# 19V_Supply.net
KiCad netlist of a schematic drawn in Altium Designer
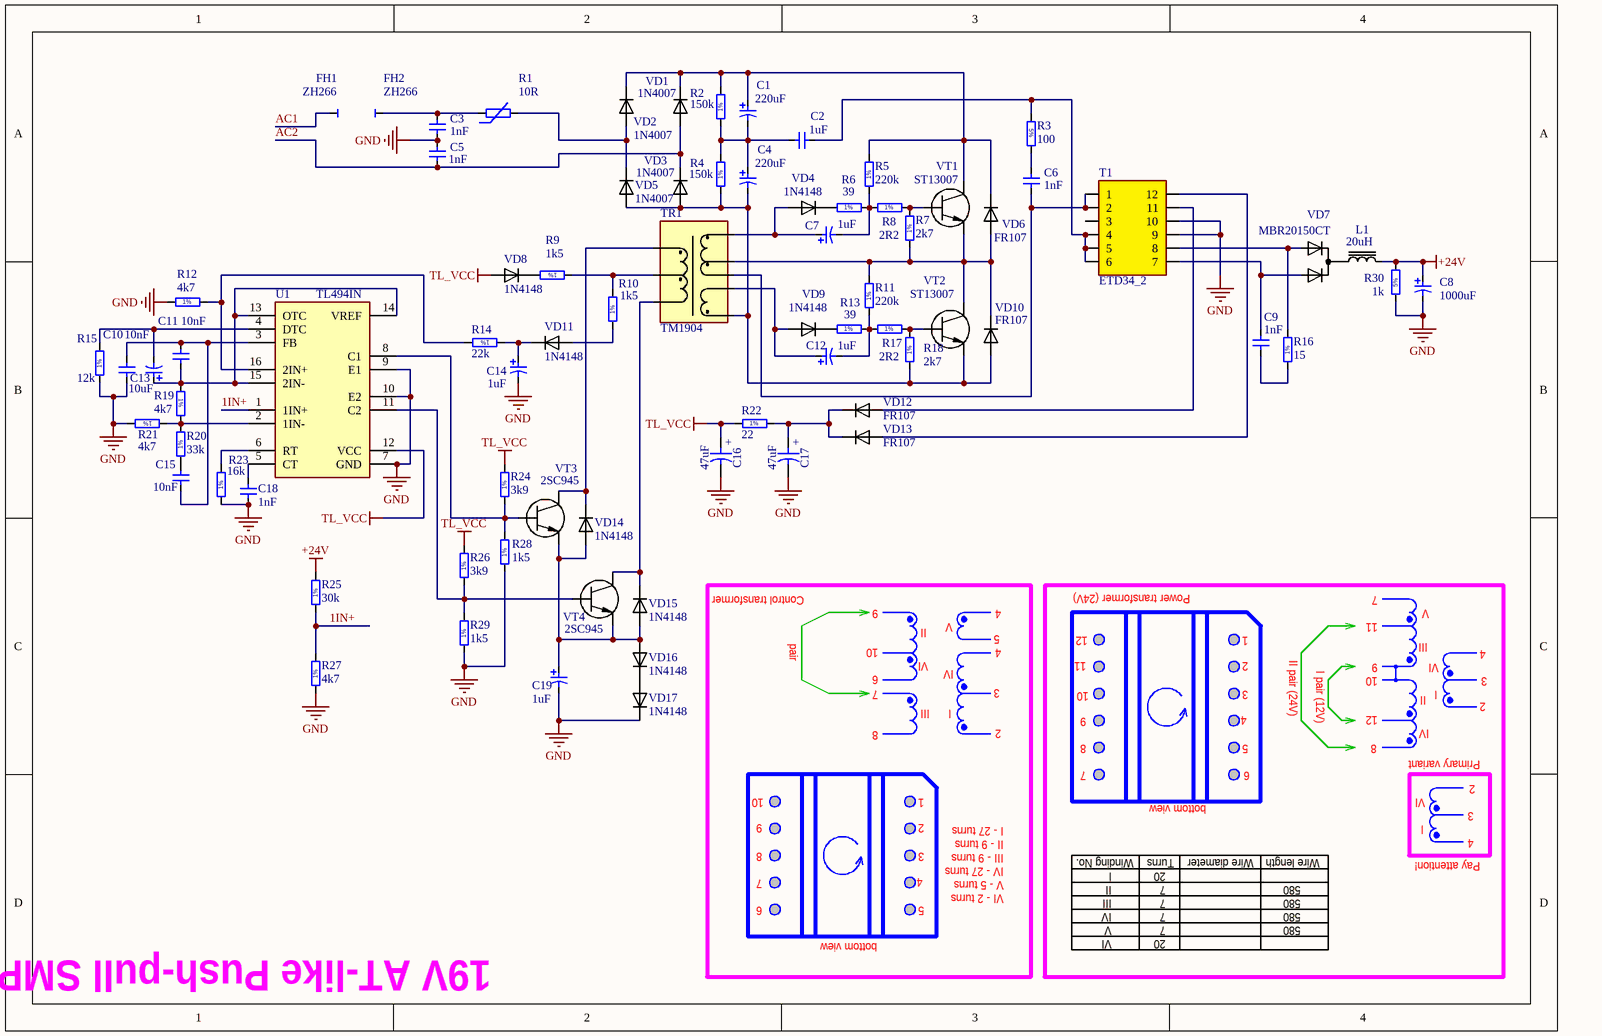
[diagram p0: 19V_Supply.SchDoc]

(export (version "E")
  (design (tool "Eeschema 10.0.6"))
  (components
    (comp (ref "C1")
      (value "220uF")
      (footprint "CAP_EL_22_25_VERT")
      (fields
        (field (name "PART NUMBER") "LG200M0220BPF-2225 (VERT MOUNTED)")
        (field (name "VOLTAGE") "200V")
      )
      (libsource (lib "Capacitor") (part "CAP_POLAR"))
    )
    (comp (ref "C2")
      (value "1uF")
      (footprint "CAPRR2000W80L2400T750H1500_CL21")
      (description "SMD 0805 Capacitor")
      (fields (field (name "PART NUMBER") "К73-17-250-1 10%") (field (name "VOLTAGE") "250V"))
      (libsource (lib "Capacitor") (part "CAP_NON_POLAR"))
    )
    (comp (ref "C3")
      (value "1nF")
      (footprint "CAP_5.0MM")
      (description "SMD 0805 Capacitor")
      (fields (field (name "PART NUMBER") "CK45-B3DD102KYNN") (field (name "VOLTAGE") "2000V"))
      (libsource (lib "Capacitor") (part "CAP_NON_POLAR"))
    )
    (comp (ref "C4")
      (value "220uF")
      (footprint "CAP_EL_22_25_VERT")
      (fields
        (field (name "PART NUMBER") "LG200M0220BPF-2225 (VERT MOUNTED)")
        (field (name "VOLTAGE") "200V")
      )
      (libsource (lib "Capacitor") (part "CAP_POLAR"))
    )
    (comp (ref "C5")
      (value "1nF")
      (footprint "CAP_5.0MM")
      (description "SMD 0805 Capacitor")
      (fields (field (name "PART NUMBER") "CK45-B3DD102KYNN") (field (name "VOLTAGE") "2000V"))
      (libsource (lib "Capacitor") (part "CAP_NON_POLAR"))
    )
    (comp (ref "C6")
      (value "1nF")
      (footprint "CAP_5.0MM")
      (description "SMD 0805 Capacitor")
      (fields (field (name "PART NUMBER") "CK45-B3DD102KYNN") (field (name "VOLTAGE") "2000V"))
      (libsource (lib "Capacitor") (part "CAP_NON_POLAR"))
    )
    (comp (ref "C7")
      (value "1uF")
      (footprint "CAP_EL_05_11_VERT")
      (fields (field (name "PART NUMBER") "SH050M1R00B2F-0511 (VERT MOUNTED)") (field (name "VOLTAGE") "50V"))
      (libsource (lib "Capacitor") (part "CAP_POLAR"))
    )
    (comp (ref "C8")
      (value "1000uF")
      (footprint "CAP_EL_13_20_VERT")
      (fields (field (name "PART NUMBER") "SK035M1000B5S-1320 (VERT MOUNTED)") (field (name "VOLTAGE") "35V"))
      (libsource (lib "Capacitor") (part "CAP_POLAR"))
    )
    (comp (ref "C9")
      (value "1nF")
      (footprint "CAP_5.0MM")
      (description "SMD 0805 Capacitor")
      (fields (field (name "PART NUMBER") "CK45-B3DD102KYNN") (field (name "VOLTAGE") "2000V"))
      (libsource (lib "Capacitor") (part "CAP_NON_POLAR"))
    )
    (comp (ref "C10")
      (value "10nF")
      (footprint "CAP_5.0MM")
      (description "SMD 0805 Capacitor")
      (fields (field (name "PART NUMBER") "TS170R1H103K8BBB0R") (field (name "VOLTAGE") "50V"))
      (libsource (lib "Capacitor") (part "CAP_NON_POLAR"))
    )
    (comp (ref "C11")
      (value "10nF")
      (footprint "CAP_5.0MM")
      (description "SMD 0805 Capacitor")
      (fields (field (name "PART NUMBER") "TS170R1H103K8BBB0R") (field (name "VOLTAGE") "50V"))
      (libsource (lib "Capacitor") (part "CAP_NON_POLAR"))
    )
    (comp (ref "C12")
      (value "1uF")
      (footprint "CAP_EL_05_11_VERT")
      (fields (field (name "PART NUMBER") "SH050M1R00B2F-0511 (VERT MOUNTED)") (field (name "VOLTAGE") "50V"))
      (libsource (lib "Capacitor") (part "CAP_POLAR"))
    )
    (comp (ref "C13")
      (value "10uF")
      (footprint "CAP_EL_05_11_VERT")
      (fields (field (name "PART NUMBER") "SH050M0010B2F-0511 (VERT MOUNTED)") (field (name "VOLTAGE") "50V"))
      (libsource (lib "Capacitor") (part "CAP_POLAR"))
    )
    (comp (ref "C14")
      (value "1uF")
      (footprint "CAP_EL_05_11_VERT")
      (fields (field (name "PART NUMBER") "SH050M1R00B2F-0511 (VERT MOUNTED)") (field (name "VOLTAGE") "50V"))
      (libsource (lib "Capacitor") (part "CAP_POLAR"))
    )
    (comp (ref "C15")
      (value "10nF")
      (footprint "CAP_5.0MM")
      (description "SMD 0805 Capacitor")
      (fields (field (name "PART NUMBER") "TS170R1H103K8BBB0R") (field (name "VOLTAGE") "50V"))
      (libsource (lib "Capacitor") (part "CAP_NON_POLAR"))
    )
    (comp (ref "C16")
      (value "47uF")
      (footprint "CAPPR250-500X1100")
      (description "Polarised capacitor")
      (fields
        (field (name "PART NUMBER") "CAER_47UF_25V_20%_250-500X1100")
        (field (name "VOLTAGE") "25V")
        (field (name "AUTHOR") "CERN DEM JLC")
      )
      (libsource (lib "Capacitors") (part "Capacitor - polarized"))
    )
    (comp (ref "C17")
      (value "47uF")
      (footprint "CAPPR250-500X1100")
      (description "Polarised capacitor")
      (fields
        (field (name "PART NUMBER") "CAER_47UF_25V_20%_250-500X1100")
        (field (name "VOLTAGE") "25V")
        (field (name "AUTHOR") "CERN DEM JLC")
      )
      (libsource (lib "Capacitors") (part "Capacitor - polarized"))
    )
    (comp (ref "C18")
      (value "1nF")
      (footprint "CAP_5.0MM")
      (description "SMD 0805 Capacitor")
      (fields (field (name "PART NUMBER") "TS170R1H102JSBNB0R") (field (name "VOLTAGE") "50V"))
      (libsource (lib "Capacitor") (part "CAP_NON_POLAR"))
    )
    (comp (ref "C19")
      (value "1uF")
      (footprint "CAP_EL_05_11_VERT")
      (fields (field (name "PART NUMBER") "SH050M1R00B2F-0511 (VERT MOUNTED)") (field (name "VOLTAGE") "50V"))
      (libsource (lib "Capacitor") (part "CAP_POLAR"))
    )
    (comp (ref "FH1") (value "ZH266") (footprint "ZH266") (libsource (lib "Connector") (part "Fuse Clip")))
    (comp (ref "FH2") (value "ZH266") (footprint "ZH266") (libsource (lib "Connector") (part "Fuse Clip")))
    (comp (ref "L1")
      (value "20uH")
      (footprint "DGS")
      (fields (field (name "PART NUMBER") "DGS") (field (name "TOLERANCE") "± 10%"))
      (libsource (lib "Transformer") (part "Core_Inductor"))
    )
    (comp (ref "R1")
      (value "10R")
      (footprint "B57164K")
      (fields (field (name "PART NUMBER") "B57164K"))
      (libsource (lib "Resistor") (part "Resistor - Thermo"))
    )
    (comp (ref "R2")
      (value "150k")
      (footprint "RES_AXIAL_0_25_8")
      (fields
        (field (name "PART NUMBER") "RMF_150K_1%_0.6W_50PPM_1016-630X250")
        (field (name "POWER") "0.6W")
        (field (name "TOLERANCE") "±1%")
        (field (name "AUTHOR") "CERN DEM JLC")
      )
      (libsource (lib "Resistor") (part "Resistor - 1%"))
    )
    (comp (ref "R3")
      (value "100")
      (footprint "RES_VERT_2W_5")
      (fields (field (name "PART NUMBER") "RCF_100R_5%_2W_HB"))
      (libsource (lib "Resistor") (part "Resistor - 5%"))
    )
    (comp (ref "R4")
      (value "150k")
      (footprint "RES_AXIAL_0_25_8")
      (fields
        (field (name "PART NUMBER") "RMF_150K_1%_0.6W_50PPM_1016-630X250")
        (field (name "POWER") "0.6W")
        (field (name "TOLERANCE") "±1%")
        (field (name "AUTHOR") "CERN DEM JLC")
      )
      (libsource (lib "Resistor") (part "Resistor - 1%"))
    )
    (comp (ref "R5")
      (value "220k")
      (footprint "RES_AXIAL_0_25_8")
      (fields
        (field (name "PART NUMBER") "RMF_220K_1%_0.6W_50PPM_1016-630X250")
        (field (name "POWER") "0.6W")
        (field (name "TOLERANCE") "±1%")
        (field (name "AUTHOR") "CERN DEM JLC")
      )
      (libsource (lib "Resistor") (part "Resistor - 1%"))
    )
    (comp (ref "R6")
      (value "39")
      (footprint "RES_AXIAL_0_25_8")
      (fields
        (field (name "PART NUMBER") "RMF_39R_1%_0.6W_50PPM_1016-630X250")
        (field (name "POWER") "0.6W")
        (field (name "TOLERANCE") "±1%")
        (field (name "AUTHOR") "CERN DEM JLC")
      )
      (libsource (lib "Resistor") (part "Resistor - 1%"))
    )
    (comp (ref "R7")
      (value "2k7")
      (footprint "RES_AXIAL_0_25_8")
      (fields
        (field (name "PART NUMBER") "RMF_2K7_1%_0.6W_50PPM_1016-630X250")
        (field (name "POWER") "0.6W")
        (field (name "TOLERANCE") "±1%")
        (field (name "AUTHOR") "CERN DEM JLC")
      )
      (libsource (lib "Resistor") (part "Resistor - 1%"))
    )
    (comp (ref "R8")
      (value "2R2")
      (footprint "RES_AXIAL_0_25_8")
      (fields
        (field (name "PART NUMBER") "RMF_2R2_1%_0.6W_50PPM_1016-630X250")
        (field (name "POWER") "0.6W")
        (field (name "TOLERANCE") "±1%")
        (field (name "AUTHOR") "CERN DEM JLC")
      )
      (libsource (lib "Resistor") (part "Resistor - 1%"))
    )
    (comp (ref "R9")
      (value "1k5")
      (footprint "RES_AXIAL_0_25_8")
      (fields
        (field (name "PART NUMBER") "RMF_1K5_1%_0.6W_50PPM_1016-630X250")
        (field (name "POWER") "0.6W")
        (field (name "TOLERANCE") "±1%")
        (field (name "AUTHOR") "CERN DEM JLC")
      )
      (libsource (lib "Resistor") (part "Resistor - 1%"))
    )
    (comp (ref "R10")
      (value "1k5")
      (footprint "RES_AXIAL_0_25_8")
      (fields
        (field (name "PART NUMBER") "RMF_1K5_1%_0.6W_50PPM_1016-630X250")
        (field (name "POWER") "0.6W")
        (field (name "TOLERANCE") "±1%")
        (field (name "AUTHOR") "CERN DEM JLC")
      )
      (libsource (lib "Resistor") (part "Resistor - 1%"))
    )
    (comp (ref "R11")
      (value "220k")
      (footprint "RES_AXIAL_0_25_8")
      (fields
        (field (name "PART NUMBER") "RMF_220K_1%_0.6W_50PPM_1016-630X250")
        (field (name "POWER") "0.6W")
        (field (name "TOLERANCE") "±1%")
        (field (name "AUTHOR") "CERN DEM JLC")
      )
      (libsource (lib "Resistor") (part "Resistor - 1%"))
    )
    (comp (ref "R12")
      (value "4k7")
      (footprint "RES_AXIAL_0_25_8")
      (fields
        (field (name "PART NUMBER") "RMF_4K7_1%_0.6W_50PPM_1016-630X250")
        (field (name "POWER") "0.6W")
        (field (name "TOLERANCE") "±1%")
        (field (name "AUTHOR") "CERN DEM JLC")
      )
      (libsource (lib "Resistor") (part "Resistor - 1%"))
    )
    (comp (ref "R13")
      (value "39")
      (footprint "RES_AXIAL_0_25_8")
      (fields
        (field (name "PART NUMBER") "RMF_39R_1%_0.6W_50PPM_1016-630X250")
        (field (name "POWER") "0.6W")
        (field (name "TOLERANCE") "±1%")
        (field (name "AUTHOR") "CERN DEM JLC")
      )
      (libsource (lib "Resistor") (part "Resistor - 1%"))
    )
    (comp (ref "R14")
      (value "22k")
      (footprint "RES_AXIAL_0_25_8")
      (fields
        (field (name "PART NUMBER") "RMF_22K_1%_0.6W_50PPM_1016-630X250")
        (field (name "POWER") "0.6W")
        (field (name "TOLERANCE") "±1%")
        (field (name "AUTHOR") "CERN DEM JLC")
      )
      (libsource (lib "Resistor") (part "Resistor - 1%"))
    )
    (comp (ref "R15")
      (value "12k")
      (footprint "RES_AXIAL_0_25_8")
      (fields
        (field (name "PART NUMBER") "RMF_12K_1%_0.6W_50PPM_1016-630X250")
        (field (name "POWER") "0.6W")
        (field (name "TOLERANCE") "±1%")
        (field (name "AUTHOR") "CERN DEM JLC")
      )
      (libsource (lib "Resistor") (part "Resistor - 1%"))
    )
    (comp (ref "R16")
      (value "15")
      (footprint "RES_AXIAL_0_25_8")
      (fields
        (field (name "PART NUMBER") "RMF_15R_1%_0.6W_50PPM_1016-630X250")
        (field (name "POWER") "0.6W")
        (field (name "TOLERANCE") "±1%")
        (field (name "AUTHOR") "CERN DEM JLC")
      )
      (libsource (lib "Resistor") (part "Resistor - 1%"))
    )
    (comp (ref "R17")
      (value "2R2")
      (footprint "RES_AXIAL_0_25_8")
      (fields
        (field (name "PART NUMBER") "RMF_2R2_1%_0.6W_50PPM_1016-630X250")
        (field (name "POWER") "0.6W")
        (field (name "TOLERANCE") "±1%")
        (field (name "AUTHOR") "CERN DEM JLC")
      )
      (libsource (lib "Resistor") (part "Resistor - 1%"))
    )
    (comp (ref "R18")
      (value "2k7")
      (footprint "RES_AXIAL_0_25_8")
      (fields
        (field (name "PART NUMBER") "RMF_2K7_1%_0.6W_50PPM_1016-630X250")
        (field (name "POWER") "0.6W")
        (field (name "TOLERANCE") "±1%")
        (field (name "AUTHOR") "CERN DEM JLC")
      )
      (libsource (lib "Resistor") (part "Resistor - 1%"))
    )
    (comp (ref "R19")
      (value "4k7")
      (footprint "RES_AXIAL_0_25_8")
      (fields
        (field (name "PART NUMBER") "RMF_4K7_1%_0.6W_50PPM_1016-630X250")
        (field (name "POWER") "0.6W")
        (field (name "TOLERANCE") "±1%")
        (field (name "AUTHOR") "CERN DEM JLC")
      )
      (libsource (lib "Resistor") (part "Resistor - 1%"))
    )
    (comp (ref "R20")
      (value "33k")
      (footprint "RES_AXIAL_0_25_8")
      (fields
        (field (name "PART NUMBER") "RMF_33K_1%_0.6W_50PPM_1016-630X250")
        (field (name "POWER") "0.6W")
        (field (name "TOLERANCE") "±1%")
        (field (name "AUTHOR") "CERN DEM JLC")
      )
      (libsource (lib "Resistor") (part "Resistor - 1%"))
    )
    (comp (ref "R21")
      (value "4k7")
      (footprint "RES_AXIAL_0_25_8")
      (fields
        (field (name "PART NUMBER") "RMF_4K7_1%_0.6W_50PPM_1016-630X250")
        (field (name "POWER") "0.6W")
        (field (name "TOLERANCE") "±1%")
        (field (name "AUTHOR") "CERN DEM JLC")
      )
      (libsource (lib "Resistor") (part "Resistor - 1%"))
    )
    (comp (ref "R22")
      (value "22")
      (footprint "RES_AXIAL_0_25_8")
      (fields
        (field (name "PART NUMBER") "RMF_22R_1%_0.6W_50PPM_1016-630X250")
        (field (name "POWER") "0.6W")
        (field (name "TOLERANCE") "±1%")
        (field (name "AUTHOR") "CERN DEM JLC")
      )
      (libsource (lib "Resistor") (part "Resistor - 1%"))
    )
    (comp (ref "R23")
      (value "16k")
      (footprint "RES_AXIAL_0_25_8")
      (fields
        (field (name "PART NUMBER") "RMF_16K_1%_0.6W_50PPM_1016-630X250")
        (field (name "POWER") "0.6W")
        (field (name "TOLERANCE") "±1%")
        (field (name "AUTHOR") "CERN DEM JLC")
      )
      (libsource (lib "Resistor") (part "Resistor - 1%"))
    )
    (comp (ref "R24")
      (value "3k9")
      (footprint "RES_AXIAL_0_25_8")
      (fields
        (field (name "PART NUMBER") "RMF_3K9_1%_0.6W_50PPM_1016-630X250")
        (field (name "POWER") "0.6W")
        (field (name "TOLERANCE") "±1%")
        (field (name "AUTHOR") "CERN DEM JLC")
      )
      (libsource (lib "Resistor") (part "Resistor - 1%"))
    )
    (comp (ref "R25")
      (value "30k")
      (footprint "RES_AXIAL_0_25_8")
      (fields
        (field (name "PART NUMBER") "RMF_30K_1%_0.6W_50PPM_1016-630X250")
        (field (name "POWER") "0.6W")
        (field (name "TOLERANCE") "±1%")
        (field (name "AUTHOR") "CERN DEM JLC")
      )
      (libsource (lib "Resistor") (part "Resistor - 1%"))
    )
    (comp (ref "R26")
      (value "3k9")
      (footprint "RES_AXIAL_0_25_8")
      (fields
        (field (name "PART NUMBER") "RMF_3K9_1%_0.6W_50PPM_1016-630X250")
        (field (name "POWER") "0.6W")
        (field (name "TOLERANCE") "±1%")
        (field (name "AUTHOR") "CERN DEM JLC")
      )
      (libsource (lib "Resistor") (part "Resistor - 1%"))
    )
    (comp (ref "R27")
      (value "4k7")
      (footprint "RES_AXIAL_0_25_8")
      (fields
        (field (name "PART NUMBER") "RMF_4K7_1%_0.6W_50PPM_1016-630X250")
        (field (name "POWER") "0.6W")
        (field (name "TOLERANCE") "±1%")
        (field (name "AUTHOR") "CERN DEM JLC")
      )
      (libsource (lib "Resistor") (part "Resistor - 1%"))
    )
    (comp (ref "R28")
      (value "1k5")
      (footprint "RES_AXIAL_0_25_8")
      (fields
        (field (name "PART NUMBER") "RMF_1K5_1%_0.6W_50PPM_1016-630X250")
        (field (name "POWER") "0.6W")
        (field (name "TOLERANCE") "±1%")
        (field (name "AUTHOR") "CERN DEM JLC")
      )
      (libsource (lib "Resistor") (part "Resistor - 1%"))
    )
    (comp (ref "R29")
      (value "1k5")
      (footprint "RES_AXIAL_0_25_8")
      (fields
        (field (name "PART NUMBER") "RMF_1K5_1%_0.6W_50PPM_1016-630X250")
        (field (name "POWER") "0.6W")
        (field (name "TOLERANCE") "±1%")
        (field (name "AUTHOR") "CERN DEM JLC")
      )
      (libsource (lib "Resistor") (part "Resistor - 1%"))
    )
    (comp (ref "R30")
      (value "1k")
      (footprint "RES_VERT_2W_5")
      (fields (field (name "PART NUMBER") "RCF_100R_5%_2W_HB"))
      (libsource (lib "Resistor") (part "Resistor - 5%"))
    )
    (comp (ref "T1")
      (value "ETD34_2")
      (footprint "ETD34_2")
      (fields (field (name "PART NUMBER") "ETD34/2"))
      (libsource (lib "Transformer") (part "Coil_Former_12pin"))
    )
    (comp (ref "TR1") (value "TM1904") (footprint "TM1904") (libsource (lib "Transformer") (part "TM1904")))
    (comp (ref "U1")
      (value "TL494IN")
      (footprint "DIP16")
      (libsource (lib "IC And Semiconductor") (part "TL494"))
    )
    (comp (ref "VD1")
      (value "1N4007")
      (footprint "DO-41")
      (fields (field (name "PART NUMBER") "1N4007_HOR"))
      (libsource (lib "IC And Semiconductor") (part "Diode - General"))
    )
    (comp (ref "VD2")
      (value "1N4007")
      (footprint "DO-41")
      (fields (field (name "PART NUMBER") "1N4007_HOR"))
      (libsource (lib "IC And Semiconductor") (part "Diode - General"))
    )
    (comp (ref "VD3")
      (value "1N4007")
      (footprint "DO-41")
      (fields (field (name "PART NUMBER") "1N4007_HOR"))
      (libsource (lib "IC And Semiconductor") (part "Diode - General"))
    )
    (comp (ref "VD4")
      (value "1N4148")
      (footprint "DO-35(300mil)")
      (fields (field (name "PART NUMBER") "1N4148 (300mil)"))
      (libsource (lib "IC And Semiconductor") (part "Diode - General"))
    )
    (comp (ref "VD5")
      (value "1N4007")
      (footprint "DO-41")
      (fields (field (name "PART NUMBER") "1N4007_HOR"))
      (libsource (lib "IC And Semiconductor") (part "Diode - General"))
    )
    (comp (ref "VD6")
      (value "FR107")
      (footprint "DO-41")
      (fields (field (name "PART NUMBER") "FR107 (HOR MOUNTED)"))
      (libsource (lib "IC And Semiconductor") (part "Diode - General"))
    )
    (comp (ref "VD7")
      (value "MBR20150CT")
      (footprint "TO-220-3")
      (libsource (lib "IC And Semiconductor") (part "D_3P_TO220"))
    )
    (comp (ref "VD8")
      (value "1N4148")
      (footprint "DO-35(300mil)")
      (fields (field (name "PART NUMBER") "1N4148 (300mil)"))
      (libsource (lib "IC And Semiconductor") (part "Diode - General"))
    )
    (comp (ref "VD9")
      (value "1N4148")
      (footprint "DO-35(300mil)")
      (fields (field (name "PART NUMBER") "1N4148 (300mil)"))
      (libsource (lib "IC And Semiconductor") (part "Diode - General"))
    )
    (comp (ref "VD10")
      (value "FR107")
      (footprint "DO-41")
      (fields (field (name "PART NUMBER") "FR107 (HOR MOUNTED)"))
      (libsource (lib "IC And Semiconductor") (part "Diode - General"))
    )
    (comp (ref "VD11")
      (value "1N4148")
      (footprint "DO-35(300mil)")
      (fields (field (name "PART NUMBER") "1N4148 (300mil)"))
      (libsource (lib "IC And Semiconductor") (part "Diode - General"))
    )
    (comp (ref "VD12")
      (value "FR107")
      (footprint "DO-41 (8.5mm)")
      (fields (field (name "PART NUMBER") "FR107 (HOR MOUNTED)"))
      (libsource (lib "IC And Semiconductor") (part "Diode - General"))
    )
    (comp (ref "VD13")
      (value "FR107")
      (footprint "DO-41 (8.5mm)")
      (fields (field (name "PART NUMBER") "FR107 (HOR MOUNTED)"))
      (libsource (lib "IC And Semiconductor") (part "Diode - General"))
    )
    (comp (ref "VD14")
      (value "1N4148")
      (footprint "DO-35(300mil)")
      (fields (field (name "PART NUMBER") "1N4148 (300mil)"))
      (libsource (lib "IC And Semiconductor") (part "Diode - General"))
    )
    (comp (ref "VD15")
      (value "1N4148")
      (footprint "DO-35(300mil)")
      (fields (field (name "PART NUMBER") "1N4148 (300mil)"))
      (libsource (lib "IC And Semiconductor") (part "Diode - General"))
    )
    (comp (ref "VD16")
      (value "1N4148")
      (footprint "DO-35(300mil)")
      (fields (field (name "PART NUMBER") "1N4148 (300mil)"))
      (libsource (lib "IC And Semiconductor") (part "Diode - General"))
    )
    (comp (ref "VD17")
      (value "1N4148")
      (footprint "DO-35(300mil)")
      (fields (field (name "PART NUMBER") "1N4148 (300mil)"))
      (libsource (lib "IC And Semiconductor") (part "Diode - General"))
    )
    (comp (ref "VT1")
      (value "ST13007")
      (footprint "TO-220-3")
      (fields (field (name "AUTHOR") "I. Kuznetsov"))
      (libsource (lib "IC And Semiconductor") (part "NPN_BIPOLAR_TO92"))
    )
    (comp (ref "VT2")
      (value "ST13007")
      (footprint "TO-220-3")
      (fields (field (name "AUTHOR") "I. Kuznetsov"))
      (libsource (lib "IC And Semiconductor") (part "NPN_BIPOLAR_TO92"))
    )
    (comp (ref "VT3")
      (value "2SC945")
      (footprint "TO92")
      (libsource (lib "IC And Semiconductor") (part "NPN_BIPOLAR_TO92"))
    )
    (comp (ref "VT4")
      (value "2SC945")
      (footprint "TO92")
      (libsource (lib "IC And Semiconductor") (part "NPN_BIPOLAR_TO92"))
    )
  )
  (nets
    (net (code "1") (name "+24V") (class "Default")
      (node (ref "C8") (pin "1") (pinfunction "1_1") (pintype "passive"))
      (node (ref "L1") (pin "2") (pinfunction "2_2") (pintype "passive"))
      (node (ref "R25") (pin "2") (pinfunction "2_2") (pintype "passive"))
      (node (ref "R30") (pin "2") (pinfunction "2_2") (pintype "passive"))
    )
    (net (code "2") (name "/1IN+") (class "Default")
      (node (ref "R25") (pin "1") (pinfunction "1_1") (pintype "passive"))
      (node (ref "R27") (pin "2") (pinfunction "2_2") (pintype "passive"))
      (node (ref "U1") (pin "1") (pinfunction "1IN+_1") (pintype "passive"))
    )
    (net (code "3") (name "/AC1") (class "Default")
      (node (ref "FH1") (pin "1") (pinfunction "1_1") (pintype "passive"))
    )
    (net (code "4") (name "/AC2") (class "Default")
      (node (ref "C5") (pin "1") (pinfunction "1_1") (pintype "passive"))
      (node (ref "VD1") (pin "A") (pinfunction "A_A") (pintype "passive"))
      (node (ref "VD3") (pin "K") (pinfunction "K_K") (pintype "passive"))
    )
    (net (code "5") (name "GND") (class "Default")
      (node (ref "C10") (pin "1") (pinfunction "1_1") (pintype "passive"))
      (node (ref "C14") (pin "2") (pinfunction "2_2") (pintype "passive"))
      (node (ref "C16") (pin "2") (pinfunction "2_2") (pintype "passive"))
      (node (ref "C17") (pin "2") (pinfunction "2_2") (pintype "passive"))
      (node (ref "C18") (pin "1") (pinfunction "1_1") (pintype "passive"))
      (node (ref "C19") (pin "2") (pinfunction "2_2") (pintype "passive"))
      (node (ref "C3") (pin "1") (pinfunction "1_1") (pintype "passive"))
      (node (ref "C5") (pin "2") (pinfunction "2_2") (pintype "passive"))
      (node (ref "C8") (pin "2") (pinfunction "2_2") (pintype "passive"))
      (node (ref "R12") (pin "1") (pinfunction "1_1") (pintype "passive"))
      (node (ref "R15") (pin "1") (pinfunction "1_1") (pintype "passive"))
      (node (ref "R21") (pin "2") (pinfunction "2_2") (pintype "passive"))
      (node (ref "R23") (pin "1") (pinfunction "1_1") (pintype "passive"))
      (node (ref "R27") (pin "1") (pinfunction "1_1") (pintype "passive"))
      (node (ref "R28") (pin "1") (pinfunction "1_1") (pintype "passive"))
      (node (ref "R29") (pin "1") (pinfunction "1_1") (pintype "passive"))
      (node (ref "R30") (pin "1") (pinfunction "1_1") (pintype "passive"))
      (node (ref "T1") (pin "10") (pinfunction "10_10") (pintype "passive"))
      (node (ref "T1") (pin "9") (pinfunction "9_9") (pintype "passive"))
      (node (ref "U1") (pin "10") (pinfunction "E2_10") (pintype "passive"))
      (node (ref "U1") (pin "7") (pinfunction "GND_7") (pintype "passive"))
      (node (ref "U1") (pin "9") (pinfunction "E1_9") (pintype "passive"))
      (node (ref "VD17") (pin "K") (pinfunction "K_K") (pintype "passive"))
    )
    (net (code "6") (name "Net-(C1-Pad2)") (class "Default")
      (node (ref "C1") (pin "2") (pinfunction "2_2") (pintype "passive"))
      (node (ref "C2") (pin "1") (pinfunction "1_1") (pintype "passive"))
      (node (ref "C4") (pin "1") (pinfunction "1_1") (pintype "passive"))
      (node (ref "R2") (pin "1") (pinfunction "1_1") (pintype "passive"))
      (node (ref "R4") (pin "2") (pinfunction "2_2") (pintype "passive"))
    )
    (net (code "7") (name "Net-(C2-Pad2)") (class "Default")
      (node (ref "C2") (pin "2") (pinfunction "2_2") (pintype "passive"))
      (node (ref "R3") (pin "1") (pinfunction "1_1") (pintype "passive"))
      (node (ref "T1") (pin "4") (pinfunction "4_4") (pintype "passive"))
      (node (ref "T1") (pin "5") (pinfunction "5_5") (pintype "passive"))
      (node (ref "T1") (pin "6") (pinfunction "6_6") (pintype "passive"))
    )
    (net (code "8") (name "Net-(C3-Pad2)") (class "Default")
      (node (ref "C3") (pin "2") (pinfunction "2_2") (pintype "passive"))
      (node (ref "FH2") (pin "1") (pinfunction "1_1") (pintype "passive"))
      (node (ref "R1") (pin "1") (pinfunction "1_1") (pintype "passive"))
    )
    (net (code "9") (name "Net-(C6-Pad1)") (class "Default")
      (node (ref "C6") (pin "1") (pinfunction "1_1") (pintype "passive"))
      (node (ref "T1") (pin "1") (pinfunction "1_1") (pintype "passive"))
      (node (ref "T1") (pin "2") (pinfunction "2_2") (pintype "passive"))
      (node (ref "TR1") (pin "6") (pinfunction "6_6") (pintype "passive"))
    )
    (net (code "10") (name "Net-(C6-Pad2)") (class "Default")
      (node (ref "C6") (pin "2") (pinfunction "2_2") (pintype "passive"))
      (node (ref "R3") (pin "2") (pinfunction "2_2") (pintype "passive"))
    )
    (net (code "11") (name "Net-(C7-Pad1)") (class "Default")
      (node (ref "C7") (pin "1") (pinfunction "1_1") (pintype "passive"))
      (node (ref "TR1") (pin "9") (pinfunction "9_9") (pintype "passive"))
      (node (ref "VD4") (pin "A") (pinfunction "A_A") (pintype "passive"))
    )
    (net (code "12") (name "Net-(C7-Pad2)") (class "Default")
      (node (ref "C7") (pin "2") (pinfunction "2_2") (pintype "passive"))
      (node (ref "R5") (pin "1") (pinfunction "1_1") (pintype "passive"))
      (node (ref "R6") (pin "2") (pinfunction "2_2") (pintype "passive"))
      (node (ref "R8") (pin "1") (pinfunction "1_1") (pintype "passive"))
    )
    (net (code "13") (name "Net-(C9-Pad1)") (class "Default")
      (node (ref "C9") (pin "1") (pinfunction "1_1") (pintype "passive"))
      (node (ref "R16") (pin "1") (pinfunction "1_1") (pintype "passive"))
    )
    (net (code "14") (name "Net-(C9-Pad2)") (class "Default")
      (node (ref "C9") (pin "2") (pinfunction "2_2") (pintype "passive"))
      (node (ref "T1") (pin "7") (pinfunction "7_7") (pintype "passive"))
      (node (ref "VD7") (pin "1") (pinfunction "A_1") (pintype "passive"))
    )
    (net (code "15") (name "Net-(C12-Pad1)") (class "Default")
      (node (ref "C12") (pin "1") (pinfunction "1_1") (pintype "passive"))
      (node (ref "TR1") (pin "8") (pinfunction "8_8") (pintype "passive"))
      (node (ref "VD9") (pin "A") (pinfunction "A_A") (pintype "passive"))
    )
    (net (code "16") (name "Net-(C12-Pad2)") (class "Default")
      (node (ref "C12") (pin "2") (pinfunction "2_2") (pintype "passive"))
      (node (ref "R11") (pin "1") (pinfunction "1_1") (pintype "passive"))
      (node (ref "R13") (pin "2") (pinfunction "2_2") (pintype "passive"))
      (node (ref "R17") (pin "1") (pinfunction "1_1") (pintype "passive"))
    )
    (net (code "17") (name "Net-(C14-Pad1)") (class "Default")
      (node (ref "C14") (pin "1") (pinfunction "1_1") (pintype "passive"))
      (node (ref "R14") (pin "1") (pinfunction "1_1") (pintype "passive"))
      (node (ref "VD11") (pin "K") (pinfunction "K_K") (pintype "passive"))
    )
    (net (code "18") (name "Net-(C15-Pad2)") (class "Default")
      (node (ref "C15") (pin "2") (pinfunction "2_2") (pintype "passive"))
      (node (ref "R20") (pin "1") (pinfunction "1_1") (pintype "passive"))
    )
    (net (code "19") (name "Net-(C17-Pad1)") (class "Default")
      (node (ref "C17") (pin "1") (pinfunction "1_1") (pintype "passive"))
      (node (ref "R22") (pin "2") (pinfunction "2_2") (pintype "passive"))
      (node (ref "VD12") (pin "K") (pinfunction "K_K") (pintype "passive"))
      (node (ref "VD13") (pin "K") (pinfunction "K_K") (pintype "passive"))
    )
    (net (code "20") (name "Net-(R1-Pad2)") (class "Default")
      (node (ref "R1") (pin "2") (pinfunction "2_2") (pintype "passive"))
      (node (ref "VD2") (pin "A") (pinfunction "A_A") (pintype "passive"))
      (node (ref "VD5") (pin "K") (pinfunction "K_K") (pintype "passive"))
    )
    (net (code "21") (name "Net-(R6-Pad1)") (class "Default")
      (node (ref "R6") (pin "1") (pinfunction "1_1") (pintype "passive"))
      (node (ref "VD4") (pin "K") (pinfunction "K_K") (pintype "passive"))
    )
    (net (code "22") (name "Net-(R9-Pad2)") (class "Default")
      (node (ref "R9") (pin "2") (pinfunction "2_2") (pintype "passive"))
      (node (ref "VD8") (pin "K") (pinfunction "K_K") (pintype "passive"))
    )
    (net (code "23") (name "Net-(R10-Pad1)") (class "Default")
      (node (ref "R10") (pin "1") (pinfunction "1_1") (pintype "passive"))
      (node (ref "VD11") (pin "A") (pinfunction "A_A") (pintype "passive"))
    )
    (net (code "24") (name "Net-(R10-Pad2)") (class "Default")
      (node (ref "R10") (pin "2") (pinfunction "2_2") (pintype "passive"))
      (node (ref "R9") (pin "1") (pinfunction "1_1") (pintype "passive"))
      (node (ref "TR1") (pin "3") (pinfunction "3_3") (pintype "passive"))
    )
    (net (code "25") (name "Net-(R13-Pad1)") (class "Default")
      (node (ref "R13") (pin "1") (pinfunction "1_1") (pintype "passive"))
      (node (ref "VD9") (pin "K") (pinfunction "K_K") (pintype "passive"))
    )
    (net (code "26") (name "Net-(R16-Pad2)") (class "Default")
      (node (ref "R16") (pin "2") (pinfunction "2_2") (pintype "passive"))
      (node (ref "T1") (pin "8") (pinfunction "8_8") (pintype "passive"))
      (node (ref "VD7") (pin "3") (pinfunction "A_3") (pintype "passive"))
    )
    (net (code "27") (name "Net-(T1-Pad11)") (class "Default")
      (node (ref "T1") (pin "11") (pinfunction "11_11") (pintype "passive"))
      (node (ref "VD12") (pin "A") (pinfunction "A_A") (pintype "passive"))
    )
    (net (code "28") (name "Net-(T1-Pad12)") (class "Default")
      (node (ref "T1") (pin "12") (pinfunction "12_12") (pintype "passive"))
      (node (ref "VD13") (pin "A") (pinfunction "A_A") (pintype "passive"))
    )
    (net (code "29") (name "Net-(U1-1IN-)") (class "Default")
      (node (ref "R19") (pin "2") (pinfunction "2_2") (pintype "passive"))
      (node (ref "R20") (pin "2") (pinfunction "2_2") (pintype "passive"))
      (node (ref "R21") (pin "1") (pinfunction "1_1") (pintype "passive"))
      (node (ref "U1") (pin "2") (pinfunction "1IN-_2") (pintype "passive"))
    )
    (net (code "30") (name "Net-(U1-2IN+)") (class "Default")
      (node (ref "R12") (pin "2") (pinfunction "2_2") (pintype "passive"))
      (node (ref "R14") (pin "2") (pinfunction "2_2") (pintype "passive"))
      (node (ref "U1") (pin "16") (pinfunction "2IN+_16") (pintype "passive"))
    )
    (net (code "31") (name "Net-(U1-2IN-)") (class "Default")
      (node (ref "C11") (pin "1") (pinfunction "1_1") (pintype "passive"))
      (node (ref "C13") (pin "1") (pinfunction "1_1") (pintype "passive"))
      (node (ref "R19") (pin "1") (pinfunction "1_1") (pintype "passive"))
      (node (ref "U1") (pin "13") (pinfunction "OTC_13") (pintype "passive"))
      (node (ref "U1") (pin "14") (pinfunction "VREF_14") (pintype "passive"))
      (node (ref "U1") (pin "15") (pinfunction "2IN-_15") (pintype "passive"))
    )
    (net (code "32") (name "Net-(U1-C1)") (class "Default")
      (node (ref "R24") (pin "1") (pinfunction "1_1") (pintype "passive"))
      (node (ref "R28") (pin "2") (pinfunction "2_2") (pintype "passive"))
      (node (ref "U1") (pin "8") (pinfunction "C1_8") (pintype "passive"))
      (node (ref "VT3") (pin "1") (pinfunction "B_1") (pintype "passive"))
    )
    (net (code "33") (name "Net-(U1-C2)") (class "Default")
      (node (ref "R26") (pin "1") (pinfunction "1_1") (pintype "passive"))
      (node (ref "R29") (pin "2") (pinfunction "2_2") (pintype "passive"))
      (node (ref "U1") (pin "11") (pinfunction "C2_11") (pintype "passive"))
      (node (ref "VT4") (pin "1") (pinfunction "B_1") (pintype "passive"))
    )
    (net (code "34") (name "Net-(U1-CT)") (class "Default")
      (node (ref "C18") (pin "2") (pinfunction "2_2") (pintype "passive"))
      (node (ref "U1") (pin "5") (pinfunction "CT_5") (pintype "passive"))
    )
    (net (code "35") (name "Net-(U1-DTC)") (class "Default")
      (node (ref "C13") (pin "2") (pinfunction "2_2") (pintype "passive"))
      (node (ref "R15") (pin "2") (pinfunction "2_2") (pintype "passive"))
      (node (ref "U1") (pin "4") (pinfunction "DTC_4") (pintype "passive"))
    )
    (net (code "36") (name "Net-(U1-FB)") (class "Default")
      (node (ref "C10") (pin "2") (pinfunction "2_2") (pintype "passive"))
      (node (ref "C11") (pin "2") (pinfunction "2_2") (pintype "passive"))
      (node (ref "C15") (pin "1") (pinfunction "1_1") (pintype "passive"))
      (node (ref "U1") (pin "3") (pinfunction "FB_3") (pintype "passive"))
    )
    (net (code "37") (name "Net-(U1-RT)") (class "Default")
      (node (ref "R23") (pin "2") (pinfunction "2_2") (pintype "passive"))
      (node (ref "U1") (pin "6") (pinfunction "RT_6") (pintype "passive"))
    )
    (net (code "38") (name "Net-(VD7-K)") (class "Default")
      (node (ref "L1") (pin "1") (pinfunction "1_1") (pintype "passive"))
      (node (ref "VD7") (pin "2") (pinfunction "K_2") (pintype "passive"))
    )
    (net (code "39") (name "Net-(VD16-PadK)") (class "Default")
      (node (ref "VD16") (pin "K") (pinfunction "K_K") (pintype "passive"))
      (node (ref "VD17") (pin "A") (pinfunction "A_A") (pintype "passive"))
    )
    (net (code "40") (name "Net-(VT1-B)") (class "Default")
      (node (ref "R7") (pin "2") (pinfunction "2_2") (pintype "passive"))
      (node (ref "R8") (pin "2") (pinfunction "2_2") (pintype "passive"))
      (node (ref "VT1") (pin "1") (pinfunction "B_1") (pintype "passive"))
    )
    (net (code "41") (name "Net-(VT1-C)") (class "Default")
      (node (ref "C1") (pin "1") (pinfunction "1_1") (pintype "passive"))
      (node (ref "R2") (pin "2") (pinfunction "2_2") (pintype "passive"))
      (node (ref "R5") (pin "2") (pinfunction "2_2") (pintype "passive"))
      (node (ref "VD1") (pin "K") (pinfunction "K_K") (pintype "passive"))
      (node (ref "VD2") (pin "K") (pinfunction "K_K") (pintype "passive"))
      (node (ref "VD6") (pin "K") (pinfunction "K_K") (pintype "passive"))
      (node (ref "VT1") (pin "2") (pinfunction "C_2") (pintype "passive"))
    )
    (net (code "42") (name "Net-(VT1-E)") (class "Default")
      (node (ref "R11") (pin "2") (pinfunction "2_2") (pintype "passive"))
      (node (ref "R7") (pin "1") (pinfunction "1_1") (pintype "passive"))
      (node (ref "TR1") (pin "10") (pinfunction "10_10") (pintype "passive"))
      (node (ref "VD10") (pin "K") (pinfunction "K_K") (pintype "passive"))
      (node (ref "VD6") (pin "A") (pinfunction "A_A") (pintype "passive"))
      (node (ref "VT1") (pin "3") (pinfunction "E_3") (pintype "passive"))
      (node (ref "VT2") (pin "2") (pinfunction "C_2") (pintype "passive"))
    )
    (net (code "43") (name "Net-(VT2-B)") (class "Default")
      (node (ref "R17") (pin "2") (pinfunction "2_2") (pintype "passive"))
      (node (ref "R18") (pin "2") (pinfunction "2_2") (pintype "passive"))
      (node (ref "VT2") (pin "1") (pinfunction "B_1") (pintype "passive"))
    )
    (net (code "44") (name "Net-(VT2-E)") (class "Default")
      (node (ref "C4") (pin "2") (pinfunction "2_2") (pintype "passive"))
      (node (ref "R18") (pin "1") (pinfunction "1_1") (pintype "passive"))
      (node (ref "R4") (pin "1") (pinfunction "1_1") (pintype "passive"))
      (node (ref "TR1") (pin "7") (pinfunction "7_7") (pintype "passive"))
      (node (ref "VD10") (pin "A") (pinfunction "A_A") (pintype "passive"))
      (node (ref "VD3") (pin "A") (pinfunction "A_A") (pintype "passive"))
      (node (ref "VD5") (pin "A") (pinfunction "A_A") (pintype "passive"))
      (node (ref "VT2") (pin "3") (pinfunction "E_3") (pintype "passive"))
    )
    (net (code "45") (name "Net-(VT3-C)") (class "Default")
      (node (ref "TR1") (pin "4") (pinfunction "4_4") (pintype "passive"))
      (node (ref "VD14") (pin "K") (pinfunction "K_K") (pintype "passive"))
      (node (ref "VT3") (pin "2") (pinfunction "C_2") (pintype "passive"))
    )
    (net (code "46") (name "Net-(VT3-E)") (class "Default")
      (node (ref "C19") (pin "1") (pinfunction "1_1") (pintype "passive"))
      (node (ref "VD14") (pin "A") (pinfunction "A_A") (pintype "passive"))
      (node (ref "VD15") (pin "A") (pinfunction "A_A") (pintype "passive"))
      (node (ref "VD16") (pin "A") (pinfunction "A_A") (pintype "passive"))
      (node (ref "VT3") (pin "3") (pinfunction "E_3") (pintype "passive"))
      (node (ref "VT4") (pin "3") (pinfunction "E_3") (pintype "passive"))
    )
    (net (code "47") (name "Net-(VT4-C)") (class "Default")
      (node (ref "TR1") (pin "2") (pinfunction "2_2") (pintype "passive"))
      (node (ref "VD15") (pin "K") (pinfunction "K_K") (pintype "passive"))
      (node (ref "VT4") (pin "2") (pinfunction "C_2") (pintype "passive"))
    )
    (net (code "48") (name "TL_VCC") (class "Default")
      (node (ref "C16") (pin "1") (pinfunction "1_1") (pintype "passive"))
      (node (ref "R22") (pin "1") (pinfunction "1_1") (pintype "passive"))
      (node (ref "R24") (pin "2") (pinfunction "2_2") (pintype "passive"))
      (node (ref "R26") (pin "2") (pinfunction "2_2") (pintype "passive"))
      (node (ref "U1") (pin "12") (pinfunction "VCC_12") (pintype "passive"))
      (node (ref "VD8") (pin "A") (pinfunction "A_A") (pintype "passive"))
    )
    (net (code "49") (name "unconnected-(T1-Pad3)") (class "Default")
      (node (ref "T1") (pin "3") (pinfunction "3_3") (pintype "passive"))
    )
  )
)
